# CH340S36P-R1.net
KiCad netlist of a schematic drawn in Altium Designer
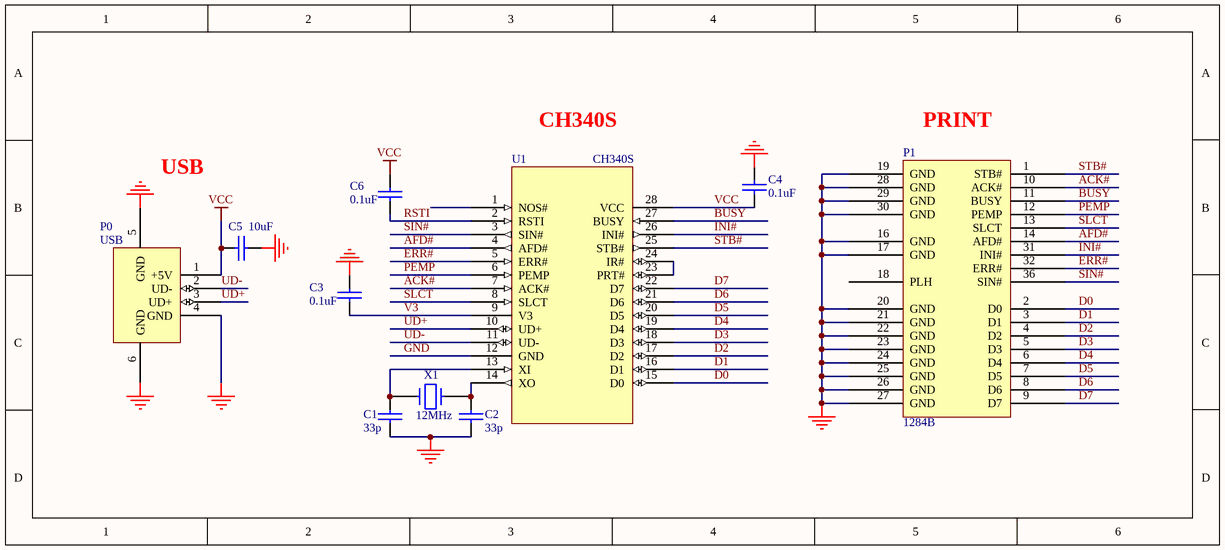
[diagram p0: CH340S36P-R1.SchDoc]

(export (version "E")
  (design (tool "Eeschema 10.0.6"))
  (components
    (comp (ref "C1") (value "33p") (footprint "0603") (libsource (lib "") (part "CAP_1")))
    (comp (ref "C2") (value "33p") (footprint "0603") (libsource (lib "") (part "CAP_1")))
    (comp (ref "C3") (value "0.1uF") (footprint "0603") (libsource (lib "") (part "CAP_1")))
    (comp (ref "C4")
      (value "0.1uF")
      (footprint "0603")
      (description "Capacitor")
      (libsource (lib "*") (part "CAP"))
    )
    (comp (ref "C5")
      (value "10uF")
      (footprint "3216")
      (description "Capacitor")
      (libsource (lib "*") (part "CAP"))
    )
    (comp (ref "C6") (value "0.1uF") (footprint "0603") (libsource (lib "") (part "CAP_1")))
    (comp (ref "P0") (value "USB") (footprint "SIP04") (libsource (lib "*") (part "USB")))
    (comp (ref "P1") (value "1284B") (footprint "1284B-DB36") (libsource (lib "*") (part "1284B")))
    (comp (ref "U1") (value "CH340S") (footprint "SOP28") (libsource (lib "*") (part "CH340S_P")))
    (comp (ref "X1")
      (value "12MHz")
      (footprint "XTAL1")
      (description "Crystal")
      (libsource (lib "*") (part "CRYSTAL"))
    )
  )
  (nets
    (net (code "1") (name "/ACK#") (class "Default")
      (node (ref "P1") (pin "10") (pinfunction "ACK#_10") (pintype "passive"))
      (node (ref "U1") (pin "7") (pinfunction "ACK#_7") (pintype "input"))
    )
    (net (code "2") (name "/AFD#") (class "Default")
      (node (ref "P1") (pin "14") (pinfunction "AFD#_14") (pintype "passive"))
      (node (ref "U1") (pin "4") (pinfunction "AFD#_4") (pintype "output"))
    )
    (net (code "3") (name "/BUSY") (class "Default")
      (node (ref "P1") (pin "11") (pinfunction "BUSY_11") (pintype "passive"))
      (node (ref "U1") (pin "27") (pinfunction "BUSY_27") (pintype "input"))
    )
    (net (code "4") (name "/D0") (class "Default")
      (node (ref "P1") (pin "2") (pinfunction "D0_2") (pintype "passive"))
      (node (ref "U1") (pin "15") (pinfunction "D0_15") (pintype "bidirectional"))
    )
    (net (code "5") (name "/D1") (class "Default")
      (node (ref "P1") (pin "3") (pinfunction "D1_3") (pintype "passive"))
      (node (ref "U1") (pin "16") (pinfunction "D1_16") (pintype "bidirectional"))
    )
    (net (code "6") (name "/D2") (class "Default")
      (node (ref "P1") (pin "4") (pinfunction "D2_4") (pintype "passive"))
      (node (ref "U1") (pin "17") (pinfunction "D2_17") (pintype "bidirectional"))
    )
    (net (code "7") (name "/D3") (class "Default")
      (node (ref "P1") (pin "5") (pinfunction "D3_5") (pintype "passive"))
      (node (ref "U1") (pin "18") (pinfunction "D3_18") (pintype "bidirectional"))
    )
    (net (code "8") (name "/D4") (class "Default")
      (node (ref "P1") (pin "6") (pinfunction "D4_6") (pintype "passive"))
      (node (ref "U1") (pin "19") (pinfunction "D4_19") (pintype "bidirectional"))
    )
    (net (code "9") (name "/D5") (class "Default")
      (node (ref "P1") (pin "7") (pinfunction "D5_7") (pintype "passive"))
      (node (ref "U1") (pin "20") (pinfunction "D5_20") (pintype "bidirectional"))
    )
    (net (code "10") (name "/D6") (class "Default")
      (node (ref "P1") (pin "8") (pinfunction "D6_8") (pintype "passive"))
      (node (ref "U1") (pin "21") (pinfunction "D6_21") (pintype "bidirectional"))
    )
    (net (code "11") (name "/D7") (class "Default")
      (node (ref "P1") (pin "9") (pinfunction "D7_9") (pintype "passive"))
      (node (ref "U1") (pin "22") (pinfunction "D7_22") (pintype "bidirectional"))
    )
    (net (code "12") (name "/ERR#") (class "Default")
      (node (ref "P1") (pin "32") (pinfunction "ERR#_32") (pintype "passive"))
      (node (ref "U1") (pin "5") (pinfunction "ERR#_5") (pintype "input"))
    )
    (net (code "13") (name "/INI#") (class "Default")
      (node (ref "P1") (pin "31") (pinfunction "INI#_31") (pintype "passive"))
      (node (ref "U1") (pin "26") (pinfunction "INI#_26") (pintype "output"))
    )
    (net (code "14") (name "/PEMP") (class "Default")
      (node (ref "P1") (pin "12") (pinfunction "PEMP_12") (pintype "passive"))
      (node (ref "U1") (pin "6") (pinfunction "PEMP_6") (pintype "input"))
    )
    (net (code "15") (name "/RSTI") (class "Default")
      (node (ref "C6") (pin "2") (pintype "passive"))
      (node (ref "U1") (pin "2") (pinfunction "RSTI_2") (pintype "input"))
    )
    (net (code "16") (name "/SIN#") (class "Default")
      (node (ref "P1") (pin "36") (pinfunction "SIN#_36") (pintype "passive"))
      (node (ref "U1") (pin "3") (pinfunction "SIN#_3") (pintype "output"))
    )
    (net (code "17") (name "/SLCT") (class "Default")
      (node (ref "P1") (pin "13") (pinfunction "SLCT_13") (pintype "passive"))
      (node (ref "U1") (pin "8") (pinfunction "SLCT_8") (pintype "input"))
    )
    (net (code "18") (name "/STB#") (class "Default")
      (node (ref "P1") (pin "1") (pinfunction "STB#_1") (pintype "passive"))
      (node (ref "U1") (pin "25") (pinfunction "STB#_25") (pintype "output"))
    )
    (net (code "19") (name "/UD+") (class "Default")
      (node (ref "P0") (pin "3") (pinfunction "UD+_3") (pintype "bidirectional"))
      (node (ref "U1") (pin "10") (pinfunction "UD+_10") (pintype "bidirectional"))
    )
    (net (code "20") (name "/UD-") (class "Default")
      (node (ref "P0") (pin "2") (pinfunction "UD-_2") (pintype "bidirectional"))
      (node (ref "U1") (pin "11") (pinfunction "UD-_11") (pintype "bidirectional"))
    )
    (net (code "21") (name "/V3") (class "Default")
      (node (ref "C3") (pin "1") (pintype "passive"))
      (node (ref "U1") (pin "9") (pinfunction "V3_9") (pintype "power_in"))
    )
    (net (code "22") (name "GND") (class "Default")
      (node (ref "C1") (pin "1") (pintype "passive"))
      (node (ref "C2") (pin "1") (pintype "passive"))
      (node (ref "C3") (pin "2") (pintype "passive"))
      (node (ref "C4") (pin "2") (pinfunction "2_2") (pintype "passive"))
      (node (ref "C5") (pin "2") (pinfunction "2_2") (pintype "passive"))
      (node (ref "P0") (pin "4") (pinfunction "GND_4") (pintype "power_in"))
      (node (ref "P0") (pin "5") (pinfunction "GND_5") (pintype "power_in"))
      (node (ref "P0") (pin "6") (pinfunction "GND_6") (pintype "power_in"))
      (node (ref "P1") (pin "16") (pinfunction "GND_16") (pintype "passive"))
      (node (ref "P1") (pin "17") (pinfunction "GND_17") (pintype "passive"))
      (node (ref "P1") (pin "19") (pinfunction "GND_19") (pintype "passive"))
      (node (ref "P1") (pin "20") (pinfunction "GND_20") (pintype "passive"))
      (node (ref "P1") (pin "21") (pinfunction "GND_21") (pintype "passive"))
      (node (ref "P1") (pin "22") (pinfunction "GND_22") (pintype "passive"))
      (node (ref "P1") (pin "23") (pinfunction "GND_23") (pintype "passive"))
      (node (ref "P1") (pin "24") (pinfunction "GND_24") (pintype "passive"))
      (node (ref "P1") (pin "25") (pinfunction "GND_25") (pintype "passive"))
      (node (ref "P1") (pin "26") (pinfunction "GND_26") (pintype "passive"))
      (node (ref "P1") (pin "27") (pinfunction "GND_27") (pintype "passive"))
      (node (ref "P1") (pin "28") (pinfunction "GND_28") (pintype "passive"))
      (node (ref "P1") (pin "29") (pinfunction "GND_29") (pintype "passive"))
      (node (ref "P1") (pin "30") (pinfunction "GND_30") (pintype "passive"))
      (node (ref "U1") (pin "12") (pinfunction "GND_12") (pintype "power_in"))
    )
    (net (code "23") (name "Net-(U1-IR#)") (class "Default")
      (node (ref "U1") (pin "23") (pinfunction "PRT#_23") (pintype "bidirectional"))
      (node (ref "U1") (pin "24") (pinfunction "IR#_24") (pintype "bidirectional"))
    )
    (net (code "24") (name "Net-(U1-XI)") (class "Default")
      (node (ref "C1") (pin "2") (pintype "passive"))
      (node (ref "U1") (pin "13") (pinfunction "XI_13") (pintype "input"))
      (node (ref "X1") (pin "1") (pinfunction "1_1") (pintype "passive"))
    )
    (net (code "25") (name "Net-(U1-XO)") (class "Default")
      (node (ref "C2") (pin "2") (pintype "passive"))
      (node (ref "U1") (pin "14") (pinfunction "XO_14") (pintype "output"))
      (node (ref "X1") (pin "2") (pinfunction "2_2") (pintype "passive"))
    )
    (net (code "26") (name "VCC") (class "Default")
      (node (ref "C4") (pin "1") (pinfunction "1_1") (pintype "passive"))
      (node (ref "C5") (pin "1") (pinfunction "1_1") (pintype "passive"))
      (node (ref "C6") (pin "1") (pintype "passive"))
      (node (ref "P0") (pin "1") (pinfunction "+5V_1") (pintype "power_in"))
      (node (ref "U1") (pin "28") (pinfunction "VCC_28") (pintype "power_in"))
    )
    (net (code "27") (name "unconnected-(P1-PLH-Pad18)") (class "Default")
      (node (ref "P1") (pin "18") (pinfunction "PLH_18") (pintype "passive"))
    )
    (net (code "28") (name "unconnected-(U1-NOS#-Pad1)") (class "Default")
      (node (ref "U1") (pin "1") (pinfunction "NOS#_1") (pintype "input"))
    )
  )
)
